# DCO.net
KiCad netlist of a schematic drawn in EAGLE
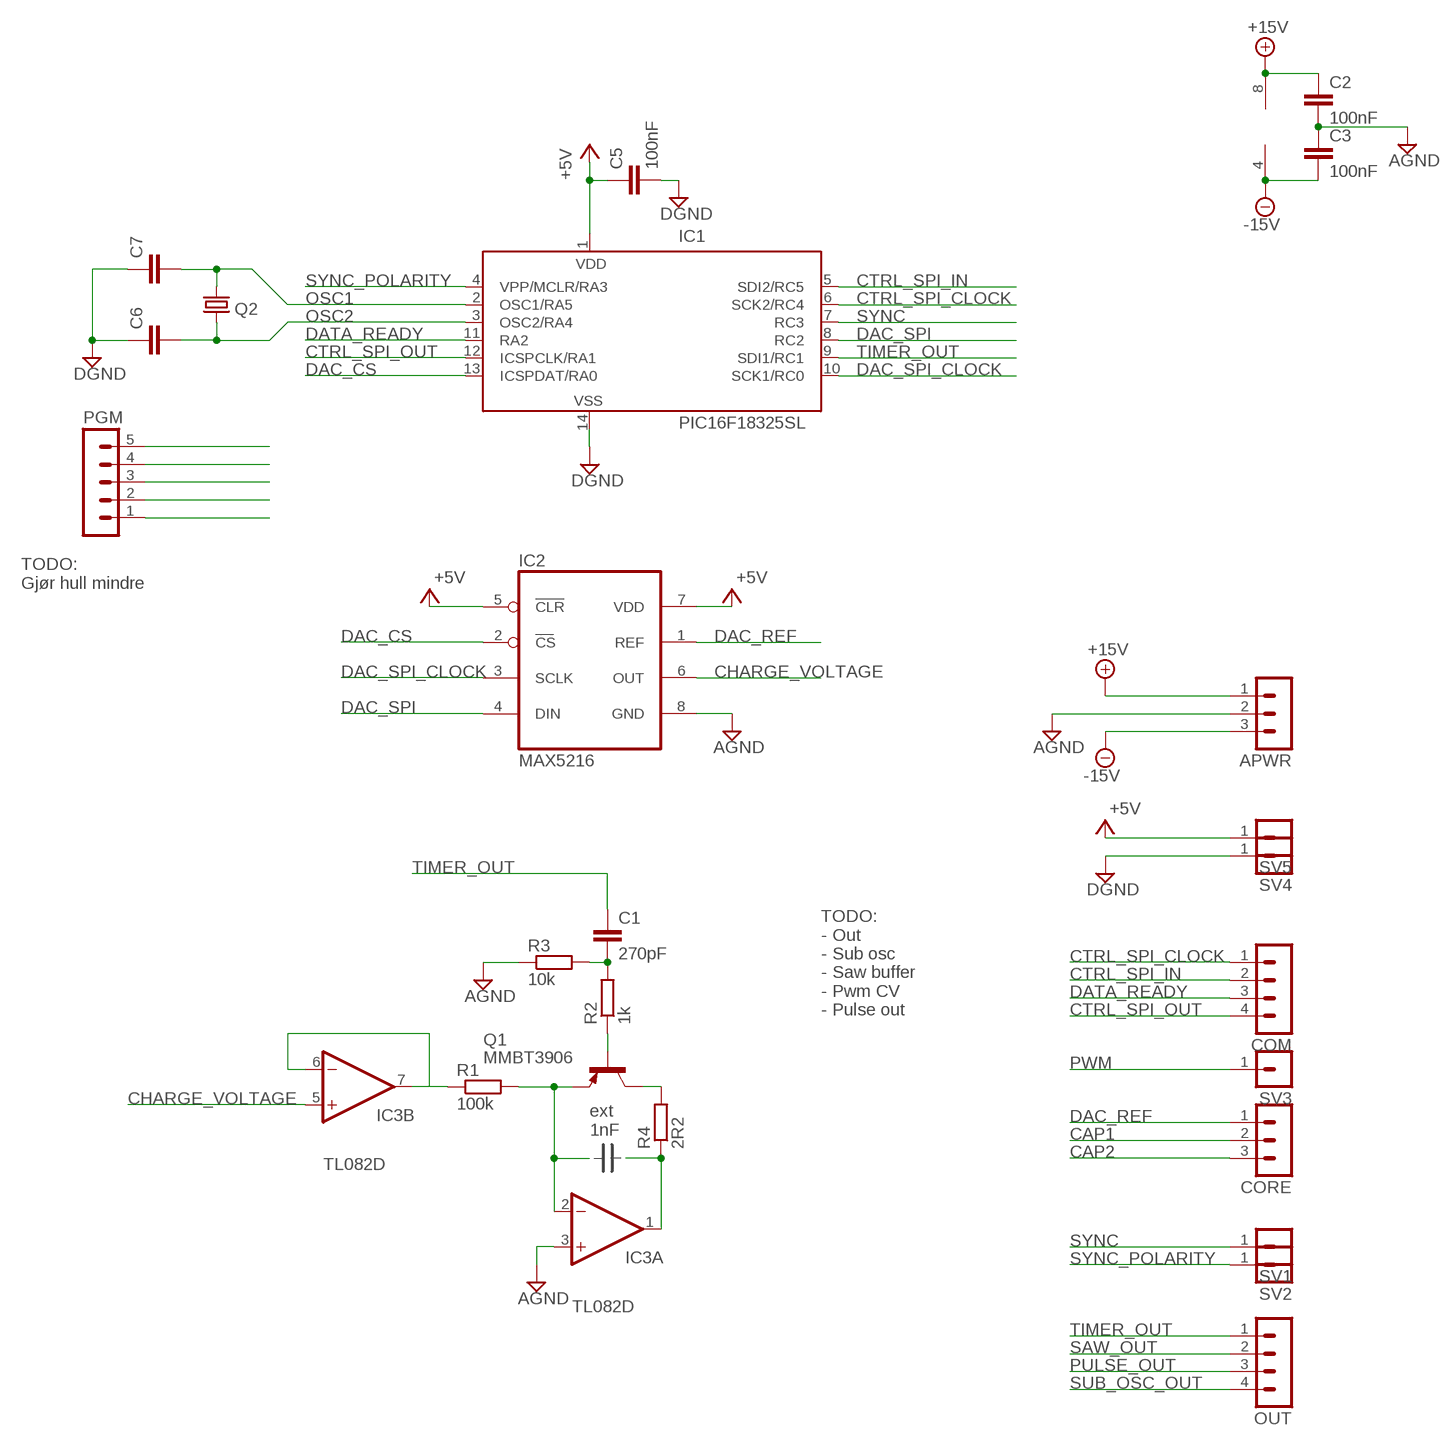
[diagram p0: schematic, sheet 1]

(export (version "E")
  (design (tool "Eeschema 10.0.6"))
  (components
    (comp (ref "APWR")
      (value "MA03-1J")
      (footprint "eagle-import:MA03-1J")
      (libsource (lib "eagle-import") (part "MA03-1J"))
    )
    (comp (ref "C1")
      (value "270pF")
      (footprint "eagle-import:C0805")
      (libsource (lib "eagle-import") (part "C-EUC0805"))
    )
    (comp (ref "C2")
      (value "100nF")
      (footprint "eagle-import:C0805")
      (libsource (lib "eagle-import") (part "C-EUC0805"))
    )
    (comp (ref "C3")
      (value "100nF")
      (footprint "eagle-import:C0805")
      (libsource (lib "eagle-import") (part "C-EUC0805"))
    )
    (comp (ref "C5")
      (value "100nF")
      (footprint "eagle-import:C0805")
      (libsource (lib "eagle-import") (part "C-EUC0805"))
    )
    (comp (ref "C6")
      (value "C-EUC0805")
      (footprint "eagle-import:C0805")
      (libsource (lib "eagle-import") (part "C-EUC0805"))
    )
    (comp (ref "C7")
      (value "C-EUC0805")
      (footprint "eagle-import:C0805")
      (libsource (lib "eagle-import") (part "C-EUC0805"))
    )
    (comp (ref "COM")
      (value "MA04-1J")
      (footprint "eagle-import:MA04-1J")
      (libsource (lib "eagle-import") (part "MA04-1J"))
    )
    (comp (ref "CORE")
      (value "MA03-1J")
      (footprint "eagle-import:MA03-1J")
      (libsource (lib "eagle-import") (part "MA03-1J"))
    )
    (comp (ref "IC1")
      (value "PIC16F18325SL")
      (footprint "eagle-import:SO14J")
      (fields (field (name "MF") "MICROCHIP") (field (name "MPN") "PIC16F676-I/SL"))
      (libsource (lib "eagle-import") (part "PIC16F18325SL"))
    )
    (comp (ref "IC2")
      (value "MAX5216")
      (footprint "eagle-import:UMAX8J")
      (libsource (lib "eagle-import") (part "MAX5216"))
    )
    (comp (ref "IC3")
      (value "TL082D")
      (footprint "eagle-import:SO08")
      (libsource (lib "eagle-import") (part "TL082D"))
    )
    (comp (ref "OUT")
      (value "MA04-1J")
      (footprint "eagle-import:MA04-1J")
      (libsource (lib "eagle-import") (part "MA04-1J"))
    )
    (comp (ref "PGM")
      (value "MA05-1J")
      (footprint "eagle-import:MA05-1J")
      (libsource (lib "eagle-import") (part "MA05-1J"))
    )
    (comp (ref "Q1")
      (value "MMBT3906")
      (footprint "eagle-import:SOT23-BEC")
      (libsource (lib "eagle-import") (part "MMBT3906SMDLT1"))
    )
    (comp (ref "Q2")
      (value "CRYSTALHC49S")
      (footprint "eagle-import:HC49_S")
      (libsource (lib "eagle-import") (part "CRYSTALHC49S"))
    )
    (comp (ref "R1")
      (value "100k")
      (footprint "eagle-import:R0805")
      (libsource (lib "eagle-import") (part "R-EU_R0805"))
    )
    (comp (ref "R2")
      (value "1k")
      (footprint "eagle-import:R0805")
      (libsource (lib "eagle-import") (part "R-EU_R0805"))
    )
    (comp (ref "R3")
      (value "10k")
      (footprint "eagle-import:R0805")
      (libsource (lib "eagle-import") (part "R-EU_R0805"))
    )
    (comp (ref "R4")
      (value "2R2")
      (footprint "eagle-import:R0805")
      (libsource (lib "eagle-import") (part "R-EU_R0805"))
    )
    (comp (ref "SV1")
      (value "MA01-1J")
      (footprint "eagle-import:MA01-1J")
      (libsource (lib "eagle-import") (part "MA01-1J"))
    )
    (comp (ref "SV2")
      (value "MA01-1J")
      (footprint "eagle-import:MA01-1J")
      (libsource (lib "eagle-import") (part "MA01-1J"))
    )
    (comp (ref "SV3")
      (value "MA01-1J")
      (footprint "eagle-import:MA01-1J")
      (libsource (lib "eagle-import") (part "MA01-1J"))
    )
    (comp (ref "SV4")
      (value "MA01-1J")
      (footprint "eagle-import:MA01-1J")
      (libsource (lib "eagle-import") (part "MA01-1J"))
    )
    (comp (ref "SV5")
      (value "MA01-1J")
      (footprint "eagle-import:MA01-1J")
      (libsource (lib "eagle-import") (part "MA01-1J"))
    )
  )
  (nets
    (net (code "1") (name "+5V") (class "Default")
      (node (ref "C5") (pin "1") (pinfunction "1_1") (pintype "passive"))
      (node (ref "IC1") (pin "1") (pinfunction "VDD_1") (pintype "power_in"))
      (node (ref "IC2") (pin "5") (pinfunction "CLR_5") (pintype "input"))
      (node (ref "IC2") (pin "7") (pinfunction "VDD_7") (pintype "power_in"))
      (node (ref "SV5") (pin "1") (pinfunction "1_1") (pintype "passive"))
    )
    (net (code "2") (name "+15V") (class "Default")
      (node (ref "APWR") (pin "1") (pinfunction "1_1") (pintype "passive"))
      (node (ref "C2") (pin "1") (pinfunction "1_1") (pintype "passive"))
      (node (ref "IC3") (pin "8") (pinfunction "V+_8") (pintype "power_in"))
    )
    (net (code "3") (name "-15V") (class "Default")
      (node (ref "APWR") (pin "3") (pinfunction "3_3") (pintype "passive"))
      (node (ref "C3") (pin "2") (pinfunction "2_2") (pintype "passive"))
      (node (ref "IC3") (pin "4") (pinfunction "V-_4") (pintype "power_in"))
    )
    (net (code "4") (name "/CAP1") (class "Default")
      (node (ref "CORE") (pin "2") (pinfunction "2_2") (pintype "passive"))
      (node (ref "IC3") (pin "2") (pinfunction "-IN_2") (pintype "input"))
      (node (ref "Q1") (pin "E") (pinfunction "E_E") (pintype "passive"))
      (node (ref "R1") (pin "2") (pinfunction "2_2") (pintype "passive"))
    )
    (net (code "5") (name "/CAP2") (class "Default")
      (node (ref "CORE") (pin "3") (pinfunction "3_3") (pintype "passive"))
      (node (ref "IC3") (pin "1") (pinfunction "OUT_1") (pintype "output"))
      (node (ref "R4") (pin "1") (pinfunction "1_1") (pintype "passive"))
    )
    (net (code "6") (name "/CHARGE_VOLTAGE") (class "Default")
      (node (ref "IC2") (pin "6") (pinfunction "OUT_6") (pintype "power_in"))
      (node (ref "IC3") (pin "5") (pinfunction "+IN_5") (pintype "input"))
    )
    (net (code "7") (name "/CTRL_SPI_CLOCK") (class "Default")
      (node (ref "COM") (pin "1") (pinfunction "1_1") (pintype "passive"))
      (node (ref "IC1") (pin "6") (pinfunction "SCK2/RC4_6") (pintype "bidirectional"))
    )
    (net (code "8") (name "/CTRL_SPI_IN") (class "Default")
      (node (ref "COM") (pin "2") (pinfunction "2_2") (pintype "passive"))
      (node (ref "IC1") (pin "5") (pinfunction "SDI2/RC5_5") (pintype "bidirectional"))
    )
    (net (code "9") (name "/CTRL_SPI_OUT") (class "Default")
      (node (ref "COM") (pin "4") (pinfunction "4_4") (pintype "passive"))
      (node (ref "IC1") (pin "12") (pinfunction "ICSPCLK/RA1_12") (pintype "bidirectional"))
    )
    (net (code "10") (name "/DAC_CS") (class "Default")
      (node (ref "IC1") (pin "13") (pinfunction "ICSPDAT/RA0_13") (pintype "bidirectional"))
      (node (ref "IC2") (pin "2") (pinfunction "CS_2") (pintype "input"))
    )
    (net (code "11") (name "/DAC_REF") (class "Default")
      (node (ref "CORE") (pin "1") (pinfunction "1_1") (pintype "passive"))
      (node (ref "IC2") (pin "1") (pinfunction "REF_1") (pintype "input"))
    )
    (net (code "12") (name "/DAC_SPI") (class "Default")
      (node (ref "IC1") (pin "8") (pinfunction "RC2_8") (pintype "bidirectional"))
      (node (ref "IC2") (pin "4") (pinfunction "DIN_4") (pintype "input"))
    )
    (net (code "13") (name "/DAC_SPI_CLOCK") (class "Default")
      (node (ref "IC1") (pin "10") (pinfunction "SCK1/RC0_10") (pintype "bidirectional"))
      (node (ref "IC2") (pin "3") (pinfunction "SCLK_3") (pintype "input"))
    )
    (net (code "14") (name "/DATA_READY") (class "Default")
      (node (ref "COM") (pin "3") (pinfunction "3_3") (pintype "passive"))
      (node (ref "IC1") (pin "11") (pinfunction "RA2_11") (pintype "bidirectional"))
    )
    (net (code "15") (name "/OSC1") (class "Default")
      (node (ref "C7") (pin "2") (pinfunction "2_2") (pintype "passive"))
      (node (ref "IC1") (pin "2") (pinfunction "OSC1/RA5_2") (pintype "bidirectional"))
      (node (ref "Q2") (pin "2") (pinfunction "2_2") (pintype "passive"))
    )
    (net (code "16") (name "/OSC2") (class "Default")
      (node (ref "C6") (pin "2") (pinfunction "2_2") (pintype "passive"))
      (node (ref "IC1") (pin "3") (pinfunction "OSC2/RA4_3") (pintype "bidirectional"))
      (node (ref "Q2") (pin "1") (pinfunction "1_1") (pintype "passive"))
    )
    (net (code "17") (name "/PULSE_OUT") (class "Default")
      (node (ref "OUT") (pin "3") (pinfunction "3_3") (pintype "passive"))
    )
    (net (code "18") (name "/PWM") (class "Default")
      (node (ref "SV3") (pin "1") (pinfunction "1_1") (pintype "passive"))
    )
    (net (code "19") (name "/SAW_OUT") (class "Default")
      (node (ref "OUT") (pin "2") (pinfunction "2_2") (pintype "passive"))
    )
    (net (code "20") (name "/SUB_OSC_OUT") (class "Default")
      (node (ref "OUT") (pin "4") (pinfunction "4_4") (pintype "passive"))
    )
    (net (code "21") (name "/SYNC") (class "Default")
      (node (ref "IC1") (pin "7") (pinfunction "RC3_7") (pintype "bidirectional"))
      (node (ref "SV1") (pin "1") (pinfunction "1_1") (pintype "passive"))
    )
    (net (code "22") (name "/SYNC_POLARITY") (class "Default")
      (node (ref "IC1") (pin "4") (pinfunction "VPP/MCLR/RA3_4") (pintype "input"))
      (node (ref "SV2") (pin "1") (pinfunction "1_1") (pintype "passive"))
    )
    (net (code "23") (name "/TIMER_OUT") (class "Default")
      (node (ref "C1") (pin "1") (pinfunction "1_1") (pintype "passive"))
      (node (ref "IC1") (pin "9") (pinfunction "SDI1/RC1_9") (pintype "bidirectional"))
      (node (ref "OUT") (pin "1") (pinfunction "1_1") (pintype "passive"))
    )
    (net (code "24") (name "AGND") (class "Default")
      (node (ref "APWR") (pin "2") (pinfunction "2_2") (pintype "passive"))
      (node (ref "C2") (pin "2") (pinfunction "2_2") (pintype "passive"))
      (node (ref "C3") (pin "1") (pinfunction "1_1") (pintype "passive"))
      (node (ref "IC2") (pin "8") (pinfunction "GND_8") (pintype "power_in"))
      (node (ref "IC3") (pin "3") (pinfunction "+IN_3") (pintype "input"))
      (node (ref "R3") (pin "1") (pinfunction "1_1") (pintype "passive"))
    )
    (net (code "25") (name "DGND") (class "Default")
      (node (ref "C5") (pin "2") (pinfunction "2_2") (pintype "passive"))
      (node (ref "C6") (pin "1") (pinfunction "1_1") (pintype "passive"))
      (node (ref "C7") (pin "1") (pinfunction "1_1") (pintype "passive"))
      (node (ref "IC1") (pin "14") (pinfunction "VSS_14") (pintype "power_in"))
      (node (ref "SV4") (pin "1") (pinfunction "1_1") (pintype "passive"))
    )
    (net (code "26") (name "Net-(C1-Pad2)") (class "Default")
      (node (ref "C1") (pin "2") (pinfunction "2_2") (pintype "passive"))
      (node (ref "R2") (pin "2") (pinfunction "2_2") (pintype "passive"))
      (node (ref "R3") (pin "2") (pinfunction "2_2") (pintype "passive"))
    )
    (net (code "27") (name "Net-(IC3B--IN)") (class "Default")
      (node (ref "IC3") (pin "6") (pinfunction "-IN_6") (pintype "input"))
      (node (ref "IC3") (pin "7") (pinfunction "OUT_7") (pintype "output"))
      (node (ref "R1") (pin "1") (pinfunction "1_1") (pintype "passive"))
    )
    (net (code "28") (name "Net-(Q1-PadB)") (class "Default")
      (node (ref "Q1") (pin "B") (pinfunction "B_B") (pintype "passive"))
      (node (ref "R2") (pin "1") (pinfunction "1_1") (pintype "passive"))
    )
    (net (code "29") (name "Net-(Q1-PadC)") (class "Default")
      (node (ref "Q1") (pin "C") (pinfunction "C_C") (pintype "passive"))
      (node (ref "R4") (pin "2") (pinfunction "2_2") (pintype "passive"))
    )
    (net (code "30") (name "unconnected-(PGM-Pad1)") (class "Default")
      (node (ref "PGM") (pin "1") (pinfunction "1_1") (pintype "passive"))
    )
    (net (code "31") (name "unconnected-(PGM-Pad2)") (class "Default")
      (node (ref "PGM") (pin "2") (pinfunction "2_2") (pintype "passive"))
    )
    (net (code "32") (name "unconnected-(PGM-Pad3)") (class "Default")
      (node (ref "PGM") (pin "3") (pinfunction "3_3") (pintype "passive"))
    )
    (net (code "33") (name "unconnected-(PGM-Pad4)") (class "Default")
      (node (ref "PGM") (pin "4") (pinfunction "4_4") (pintype "passive"))
    )
    (net (code "34") (name "unconnected-(PGM-Pad5)") (class "Default")
      (node (ref "PGM") (pin "5") (pinfunction "5_5") (pintype "passive"))
    )
  )
)
